# mm_robot_pcb_v2.net
KiCad netlist of a schematic drawn in EAGLE
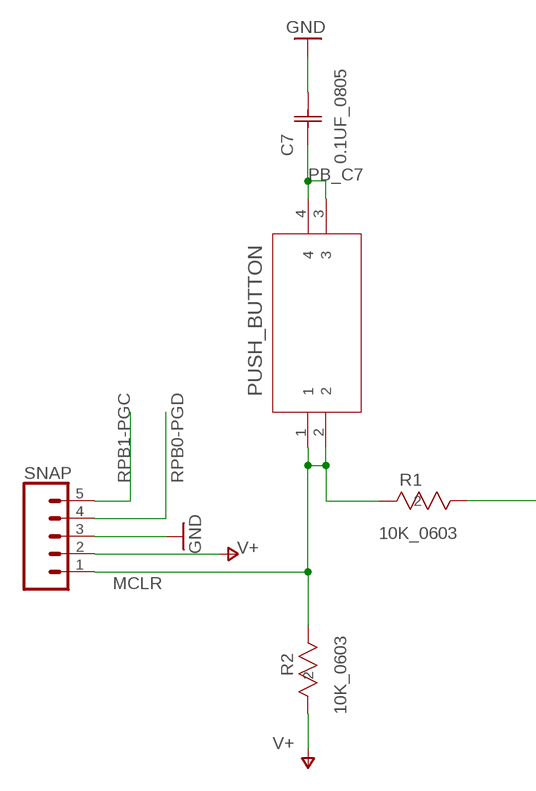
[diagram p0: schematic, sheet 1, part 1 of 2]
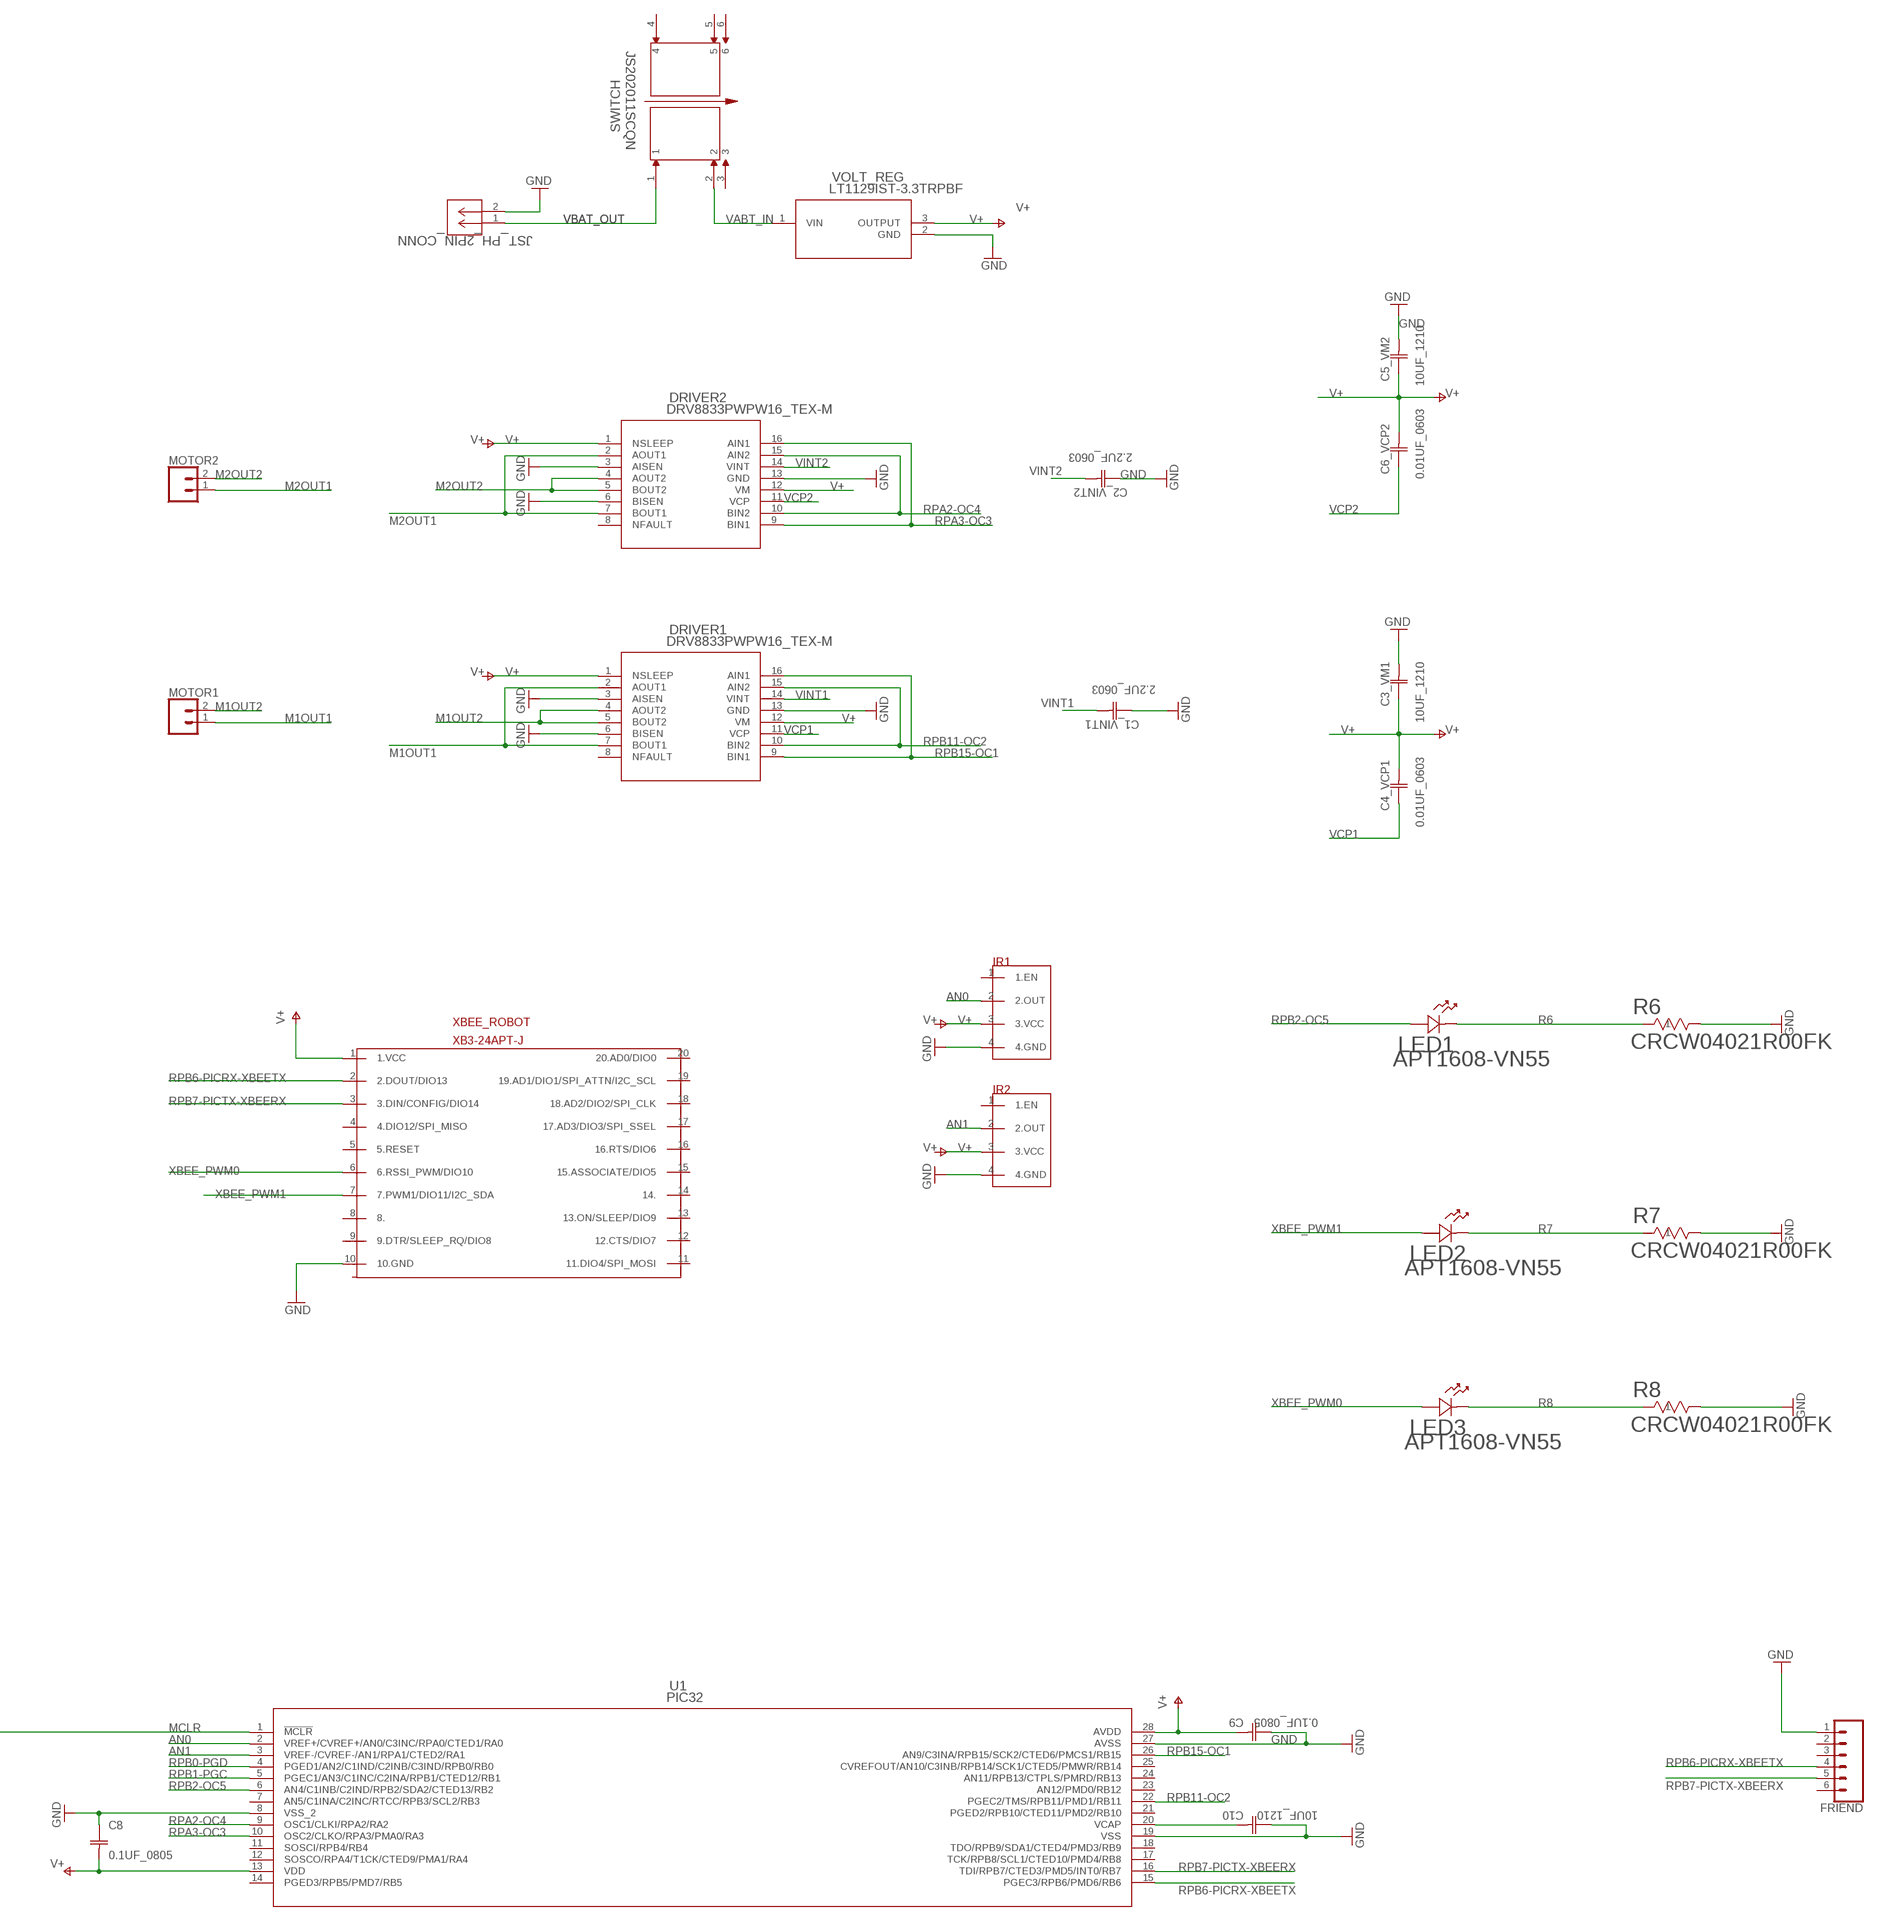
[diagram p1: schematic, sheet 1, part 2 of 2]

(export (version "E")
  (design (tool "Eeschema 10.0.6"))
  (components
    (comp (ref "C1_VINT1")
      (value "2.2UF_0603")
      (footprint "eagle-import:CAP_CL10_SAM")
      (fields
        (field (name "MANUFACTURER_PART_NUMBER") "CL10A225KP8NNNC")
        (field (name "COPYRIGHT") "Copyright (C) 2021 Ultra Librarian. All rights reserved.")
      )
      (libsource (lib "eagle-import") (part "CL10A225KP8NNNC"))
    )
    (comp (ref "C2_VINT2")
      (value "2.2UF_0603")
      (footprint "eagle-import:CAP_CL10_SAM")
      (fields
        (field (name "MANUFACTURER_PART_NUMBER") "CL10A225KP8NNNC")
        (field (name "COPYRIGHT") "Copyright (C) 2021 Ultra Librarian. All rights reserved.")
      )
      (libsource (lib "eagle-import") (part "CL10A225KP8NNNC"))
    )
    (comp (ref "C3_VM1")
      (value "10UF_1210")
      (footprint "eagle-import:CAP_TPS_B_AVX")
      (fields
        (field (name "MANUFACTURER_PART_NUMBER") "TPSB106K016R0500")
        (field (name "COPYRIGHT") "Copyright (C) 2021 Ultra Librarian. All rights reserved.")
      )
      (libsource (lib "eagle-import") (part "TPSB106K016R0500"))
    )
    (comp (ref "C4_VCP1")
      (value "0.01UF_0603")
      (footprint "eagle-import:CAP_01UF_0603_X7R_G_AVX")
      (libsource (lib "eagle-import") (part "01UF_CAP"))
    )
    (comp (ref "C5_VM2")
      (value "10UF_1210")
      (footprint "eagle-import:CAP_TPS_B_AVX")
      (fields
        (field (name "MANUFACTURER_PART_NUMBER") "TPSB106K016R0500")
        (field (name "COPYRIGHT") "Copyright (C) 2021 Ultra Librarian. All rights reserved.")
      )
      (libsource (lib "eagle-import") (part "TPSB106K016R0500"))
    )
    (comp (ref "C6_VCP2")
      (value "0.01UF_0603")
      (footprint "eagle-import:CAP_01UF_0603_X7R_G_AVX")
      (libsource (lib "eagle-import") (part "01UF_CAP"))
    )
    (comp (ref "C7")
      (value "0.1UF_0805")
      (footprint "eagle-import:CAP_C2012X7R2A104K125AA_TDK")
      (fields
        (field (name "MANUFACTURER_PART_NUMBER") "C2012X7R2A104K125AA")
        (field (name "COPYRIGHT") "Copyright (C) 2021 Ultra Librarian. All rights reserved.")
      )
      (libsource (lib "eagle-import") (part "C2012X7R2A104K125AA"))
    )
    (comp (ref "C8")
      (value "0.1UF_0805")
      (footprint "eagle-import:CAP_C2012X7R2A104K125AA_TDK")
      (fields
        (field (name "MANUFACTURER_PART_NUMBER") "C2012X7R2A104K125AA")
        (field (name "COPYRIGHT") "Copyright (C) 2021 Ultra Librarian. All rights reserved.")
      )
      (libsource (lib "eagle-import") (part "C2012X7R2A104K125AA"))
    )
    (comp (ref "C9")
      (value "0.1UF_0805")
      (footprint "eagle-import:CAP_C2012X7R2A104K125AA_TDK")
      (fields
        (field (name "MANUFACTURER_PART_NUMBER") "C2012X7R2A104K125AA")
        (field (name "COPYRIGHT") "Copyright (C) 2021 Ultra Librarian. All rights reserved.")
      )
      (libsource (lib "eagle-import") (part "C2012X7R2A104K125AA"))
    )
    (comp (ref "C10")
      (value "10UF_1210")
      (footprint "eagle-import:CAP_TPS_B_AVX")
      (fields
        (field (name "MANUFACTURER_PART_NUMBER") "TPSB106K016R0500")
        (field (name "COPYRIGHT") "Copyright (C) 2021 Ultra Librarian. All rights reserved.")
      )
      (libsource (lib "eagle-import") (part "TPSB106K016R0500"))
    )
    (comp (ref "DRIVER1")
      (value "DRV8833PWPW16_TEX-M")
      (footprint "eagle-import:PW16_TEX-M")
      (fields
        (field (name "MANUFACTURER_PART_NUMBER") "DRV8833PW")
        (field (name "COPYRIGHT") "Copyright (C) 2021 Ultra Librarian. All rights reserved.")
      )
      (libsource (lib "eagle-import") (part "DRV8833PWPW16_TEX-M"))
    )
    (comp (ref "DRIVER2")
      (value "DRV8833PWPW16_TEX-M")
      (footprint "eagle-import:PW16_TEX-M")
      (fields
        (field (name "MANUFACTURER_PART_NUMBER") "DRV8833PW")
        (field (name "COPYRIGHT") "Copyright (C) 2021 Ultra Librarian. All rights reserved.")
      )
      (libsource (lib "eagle-import") (part "DRV8833PWPW16_TEX-M"))
    )
    (comp (ref "FRIEND")
      (value "CONN_06LOCK")
      (footprint "eagle-import:1X06_LOCK")
      (libsource (lib "eagle-import") (part "CONN_06LOCK"))
    )
    (comp (ref "IR1")
      (value "GP2Y0A60SZLF")
      (footprint "eagle-import:1X04")
      (libsource (lib "eagle-import") (part "GP2Y0A60SZLF"))
    )
    (comp (ref "IR2")
      (value "GP2Y0A60SZLF")
      (footprint "eagle-import:1X04")
      (libsource (lib "eagle-import") (part "GP2Y0A60SZLF"))
    )
    (comp (ref "JST_PH_2PIN_CONN")
      (value "1769")
      (footprint "eagle-import:CONN_1769_ADA")
      (fields (field (name "COPYRIGHT") "Copyright (C) 2021 Ultra Librarian. All rights reserved."))
      (libsource (lib "eagle-import") (part "1769"))
    )
    (comp (ref "LED1")
      (value "APT1608-VN55")
      (footprint "eagle-import:LED_APT1608_KNB")
      (fields (field (name "COPYRIGHT") "Copyright (C) 2021 Ultra Librarian. All rights reserved."))
      (libsource (lib "eagle-import") (part "APT1608-VN55"))
    )
    (comp (ref "LED2")
      (value "APT1608-VN55")
      (footprint "eagle-import:LED_APT1608_KNB")
      (fields (field (name "COPYRIGHT") "Copyright (C) 2021 Ultra Librarian. All rights reserved."))
      (libsource (lib "eagle-import") (part "APT1608-VN55"))
    )
    (comp (ref "LED3")
      (value "APT1608-VN55")
      (footprint "eagle-import:LED_APT1608_KNB")
      (fields (field (name "COPYRIGHT") "Copyright (C) 2021 Ultra Librarian. All rights reserved."))
      (libsource (lib "eagle-import") (part "APT1608-VN55"))
    )
    (comp (ref "MOTOR1")
      (value "CONN_02")
      (footprint "eagle-import:1X02")
      (libsource (lib "eagle-import") (part "CONN_02"))
    )
    (comp (ref "MOTOR2")
      (value "CONN_02")
      (footprint "eagle-import:1X02")
      (libsource (lib "eagle-import") (part "CONN_02"))
    )
    (comp (ref "R1")
      (value "10K_0603")
      (footprint "eagle-import:RES0603_CRG_TYCO_TYC")
      (fields
        (field (name "MANUFACTURER_PART_NUMBER") "CRG0603F10K")
        (field (name "COPYRIGHT") "Copyright (C) 2021 Ultra Librarian. All rights reserved.")
      )
      (libsource (lib "eagle-import") (part "CRG0603F10K"))
    )
    (comp (ref "R2")
      (value "10K_0603")
      (footprint "eagle-import:RES0603_CRG_TYCO_TYC")
      (fields
        (field (name "MANUFACTURER_PART_NUMBER") "CRG0603F10K")
        (field (name "COPYRIGHT") "Copyright (C) 2021 Ultra Librarian. All rights reserved.")
      )
      (libsource (lib "eagle-import") (part "CRG0603F10K"))
    )
    (comp (ref "R6")
      (value "CRCW04021R00FK")
      (footprint "eagle-import:RES_CRCW0402_VIS")
      (fields (field (name "COPYRIGHT") "Copyright (C) 2021 Ultra Librarian. All rights reserved."))
      (libsource (lib "eagle-import") (part "CRCW04021R00FK"))
    )
    (comp (ref "R7")
      (value "CRCW04021R00FK")
      (footprint "eagle-import:RES_CRCW0402_VIS")
      (fields (field (name "COPYRIGHT") "Copyright (C) 2021 Ultra Librarian. All rights reserved."))
      (libsource (lib "eagle-import") (part "CRCW04021R00FK"))
    )
    (comp (ref "R8")
      (value "CRCW04021R00FK")
      (footprint "eagle-import:RES_CRCW0402_VIS")
      (fields (field (name "COPYRIGHT") "Copyright (C) 2021 Ultra Librarian. All rights reserved."))
      (libsource (lib "eagle-import") (part "CRCW04021R00FK"))
    )
    (comp (ref "SNAP")
      (value "CONN_05")
      (footprint "eagle-import:1X05")
      (libsource (lib "eagle-import") (part "CONN_05"))
    )
    (comp (ref "SWITCH")
      (value "JS202011SCQN")
      (footprint "eagle-import:SW_JS202011SCQN")
      (fields (field (name "COPYRIGHT") "Copyright (C) 2021 Ultra Librarian. All rights reserved."))
      (libsource (lib "eagle-import") (part "JS202011SCQN"))
    )
    (comp (ref "U1")
      (value "PIC32")
      (footprint "eagle-import:SSOP28_MC_MCH")
      (fields
        (field (name "MANUFACTURER_PART_NUMBER") "PIC32MX170F256B-I/SS")
        (field (name "COPYRIGHT") "Copyright (C) 2021 Ultra Librarian. All rights reserved.")
      )
      (libsource (lib "eagle-import") (part "PIC32MX170F256B-I/SS"))
    )
    (comp (ref "U2")
      (value "PUSH_BUTTON")
      (footprint "eagle-import:SMT_FS")
      (fields
        (field (name "MANUFACTURER_PART_NUMBER") "PTS526 SK15 SMTR2 LFS")
        (field (name "COPYRIGHT") "Copyright (C) 2021 Ultra Librarian. All rights reserved.")
      )
      (libsource (lib "eagle-import") (part "PTS526_SK15_SMTR2_LFS"))
    )
    (comp (ref "VOLT_REG")
      (value "LT1129IST-3.3TRPBF")
      (footprint "eagle-import:SOT-223_ST_LIT")
      (fields
        (field (name "MANUFACTURER_PART_NUMBER") "LT1129IST-3.3#TRPBF")
        (field (name "COPYRIGHT") "Copyright (C) 2021 Ultra Librarian. All rights reserved.")
      )
      (libsource (lib "eagle-import") (part "LT1129IST-3.3TRPBF"))
    )
    (comp (ref "XBEE_ROBOT")
      (value "XB3-24APT-J")
      (footprint "eagle-import:XB3-24APT-J")
      (libsource (lib "eagle-import") (part "XB3-24APT-J"))
    )
  )
  (nets
    (net (code "1") (name "/AN0") (class "Default")
      (node (ref "IR1") (pin "2") (pinfunction "2.OUT_2") (pintype "bidirectional"))
      (node (ref "U1") (pin "2") (pinfunction "VREF+/CVREF+/AN0/C3INC/RPA0/CTED1/RA0_2") (pintype "bidirectional"))
    )
    (net (code "2") (name "/AN1") (class "Default")
      (node (ref "IR2") (pin "2") (pinfunction "2.OUT_2") (pintype "bidirectional"))
      (node (ref "U1") (pin "3") (pinfunction "VREF-/CVREF-/AN1/RPA1/CTED2/RA1_3") (pintype "bidirectional"))
    )
    (net (code "3") (name "/M1OUT1") (class "Default")
      (node (ref "DRIVER1") (pin "2") (pinfunction "AOUT1_2") (pintype "output"))
      (node (ref "DRIVER1") (pin "7") (pinfunction "BOUT1_7") (pintype "output"))
      (node (ref "MOTOR1") (pin "1") (pinfunction "1_1") (pintype "passive"))
    )
    (net (code "4") (name "/M1OUT2") (class "Default")
      (node (ref "DRIVER1") (pin "4") (pinfunction "AOUT2_4") (pintype "output"))
      (node (ref "DRIVER1") (pin "5") (pinfunction "BOUT2_5") (pintype "output"))
      (node (ref "MOTOR1") (pin "2") (pinfunction "2_2") (pintype "passive"))
    )
    (net (code "5") (name "/M2OUT1") (class "Default")
      (node (ref "DRIVER2") (pin "2") (pinfunction "AOUT1_2") (pintype "output"))
      (node (ref "DRIVER2") (pin "7") (pinfunction "BOUT1_7") (pintype "output"))
      (node (ref "MOTOR2") (pin "1") (pinfunction "1_1") (pintype "passive"))
    )
    (net (code "6") (name "/M2OUT2") (class "Default")
      (node (ref "DRIVER2") (pin "4") (pinfunction "AOUT2_4") (pintype "output"))
      (node (ref "DRIVER2") (pin "5") (pinfunction "BOUT2_5") (pintype "output"))
      (node (ref "MOTOR2") (pin "2") (pinfunction "2_2") (pintype "passive"))
    )
    (net (code "7") (name "/MCLR") (class "Default")
      (node (ref "R1") (pin "1") (pinfunction "1_1") (pintype "passive"))
      (node (ref "R1") (pin "2") (pinfunction "2_2") (pintype "passive"))
      (node (ref "R2") (pin "1") (pinfunction "1_1") (pintype "passive"))
      (node (ref "SNAP") (pin "1") (pinfunction "1_1") (pintype "passive"))
      (node (ref "U1") (pin "1") (pinfunction "~{MCLR}_1") (pintype "bidirectional"))
      (node (ref "U2") (pin "1") (pinfunction "1_1") (pintype "passive"))
      (node (ref "U2") (pin "2") (pinfunction "2_2") (pintype "passive"))
    )
    (net (code "8") (name "/PB_C7") (class "Default")
      (node (ref "C7") (pin "1") (pinfunction "1_1") (pintype "passive"))
      (node (ref "U2") (pin "3") (pinfunction "3_3") (pintype "passive"))
      (node (ref "U2") (pin "4") (pinfunction "4_4") (pintype "passive"))
    )
    (net (code "9") (name "/R6") (class "Default")
      (node (ref "LED1") (pin "1") (pinfunction "1_1") (pintype "passive"))
      (node (ref "R6") (pin "1") (pinfunction "1_1") (pintype "passive"))
    )
    (net (code "10") (name "/R7") (class "Default")
      (node (ref "LED2") (pin "1") (pinfunction "1_1") (pintype "passive"))
      (node (ref "R7") (pin "1") (pinfunction "1_1") (pintype "passive"))
    )
    (net (code "11") (name "/R8") (class "Default")
      (node (ref "LED3") (pin "1") (pinfunction "1_1") (pintype "passive"))
      (node (ref "R8") (pin "1") (pinfunction "1_1") (pintype "passive"))
    )
    (net (code "12") (name "/RPA2-OC4") (class "Default")
      (node (ref "DRIVER2") (pin "10") (pinfunction "BIN2_10") (pintype "input"))
      (node (ref "DRIVER2") (pin "15") (pinfunction "AIN2_15") (pintype "input"))
      (node (ref "U1") (pin "9") (pinfunction "OSC1/CLKI/RPA2/RA2_9") (pintype "bidirectional"))
    )
    (net (code "13") (name "/RPA3-OC3") (class "Default")
      (node (ref "DRIVER2") (pin "16") (pinfunction "AIN1_16") (pintype "input"))
      (node (ref "DRIVER2") (pin "9") (pinfunction "BIN1_9") (pintype "input"))
      (node (ref "U1") (pin "10") (pinfunction "OSC2/CLKO/RPA3/PMA0/RA3_10") (pintype "bidirectional"))
    )
    (net (code "14") (name "/RPB0-PGD") (class "Default")
      (node (ref "SNAP") (pin "4") (pinfunction "4_4") (pintype "passive"))
      (node (ref "U1") (pin "4") (pinfunction "PGED1/AN2/C1IND/C2INB/C3IND/RPB0/RB0_4") (pintype "bidirectional"))
    )
    (net (code "15") (name "/RPB1-PGC") (class "Default")
      (node (ref "SNAP") (pin "5") (pinfunction "5_5") (pintype "passive"))
      (node (ref "U1") (pin "5") (pinfunction "PGEC1/AN3/C1INC/C2INA/RPB1/CTED12/RB1_5") (pintype "bidirectional"))
    )
    (net (code "16") (name "/RPB2-OC5") (class "Default")
      (node (ref "LED1") (pin "2") (pinfunction "2_2") (pintype "passive"))
      (node (ref "U1") (pin "6") (pinfunction "AN4/C1INB/C2IND/RPB2/SDA2/CTED13/RB2_6") (pintype "bidirectional"))
    )
    (net (code "17") (name "/RPB6-PICRX-XBEETX") (class "Default")
      (node (ref "FRIEND") (pin "4") (pinfunction "4_4") (pintype "passive"))
      (node (ref "U1") (pin "15") (pinfunction "PGEC3/RPB6/PMD6/RB6_15") (pintype "bidirectional"))
      (node (ref "XBEE_ROBOT") (pin "2") (pinfunction "2.DOUT/DIO13_2") (pintype "bidirectional"))
    )
    (net (code "18") (name "/RPB7-PICTX-XBEERX") (class "Default")
      (node (ref "FRIEND") (pin "5") (pinfunction "5_5") (pintype "passive"))
      (node (ref "U1") (pin "16") (pinfunction "TDI/RPB7/CTED3/PMD5/INT0/RB7_16") (pintype "bidirectional"))
      (node (ref "XBEE_ROBOT") (pin "3") (pinfunction "3.DIN/CONFIG/DIO14_3") (pintype "bidirectional"))
    )
    (net (code "19") (name "/RPB11-OC2") (class "Default")
      (node (ref "DRIVER1") (pin "10") (pinfunction "BIN2_10") (pintype "input"))
      (node (ref "DRIVER1") (pin "15") (pinfunction "AIN2_15") (pintype "input"))
      (node (ref "U1") (pin "22") (pinfunction "PGEC2/TMS/RPB11/PMD1/RB11_22") (pintype "bidirectional"))
    )
    (net (code "20") (name "/RPB15-OC1") (class "Default")
      (node (ref "DRIVER1") (pin "16") (pinfunction "AIN1_16") (pintype "input"))
      (node (ref "DRIVER1") (pin "9") (pinfunction "BIN1_9") (pintype "input"))
      (node (ref "U1") (pin "26") (pinfunction "AN9/C3INA/RPB15/SCK2/CTED6/PMCS1/RB15_26") (pintype "bidirectional"))
    )
    (net (code "21") (name "/VABT_IN") (class "Default")
      (node (ref "SWITCH") (pin "2") (pinfunction "2_2") (pintype "passive"))
      (node (ref "VOLT_REG") (pin "1") (pinfunction "VIN_1") (pintype "input"))
    )
    (net (code "22") (name "/VBAT_OUT") (class "Default")
      (node (ref "JST_PH_2PIN_CONN") (pin "1") (pinfunction "1_1") (pintype "passive"))
      (node (ref "SWITCH") (pin "1") (pinfunction "1_1") (pintype "passive"))
    )
    (net (code "23") (name "/VCP1") (class "Default")
      (node (ref "C4_VCP1") (pin "1") (pinfunction "1_1") (pintype "passive"))
      (node (ref "DRIVER1") (pin "11") (pinfunction "VCP_11") (pintype "bidirectional"))
    )
    (net (code "24") (name "/VCP2") (class "Default")
      (node (ref "C6_VCP2") (pin "1") (pinfunction "1_1") (pintype "passive"))
      (node (ref "DRIVER2") (pin "11") (pinfunction "VCP_11") (pintype "bidirectional"))
    )
    (net (code "25") (name "/VINT1") (class "Default")
      (node (ref "C1_VINT1") (pin "2") (pinfunction "2_2") (pintype "passive"))
      (node (ref "DRIVER1") (pin "14") (pinfunction "VINT_14") (pintype "passive"))
    )
    (net (code "26") (name "/VINT2") (class "Default")
      (node (ref "C2_VINT2") (pin "2") (pinfunction "2_2") (pintype "passive"))
      (node (ref "DRIVER2") (pin "14") (pinfunction "VINT_14") (pintype "passive"))
    )
    (net (code "27") (name "/XBEE_PWM0") (class "Default")
      (node (ref "LED3") (pin "2") (pinfunction "2_2") (pintype "passive"))
      (node (ref "XBEE_ROBOT") (pin "6") (pinfunction "6.RSSI_PWM/DIO10_6") (pintype "bidirectional"))
    )
    (net (code "28") (name "/XBEE_PWM1") (class "Default")
      (node (ref "LED2") (pin "2") (pinfunction "2_2") (pintype "passive"))
      (node (ref "XBEE_ROBOT") (pin "7") (pinfunction "7.PWM1/DIO11/I2C_SDA_7") (pintype "bidirectional"))
    )
    (net (code "29") (name "GND") (class "Default")
      (node (ref "C10") (pin "1") (pinfunction "11_1") (pintype "passive"))
      (node (ref "C1_VINT1") (pin "1") (pinfunction "1_1") (pintype "passive"))
      (node (ref "C2_VINT2") (pin "1") (pinfunction "1_1") (pintype "passive"))
      (node (ref "C3_VM1") (pin "2") (pinfunction "12_2") (pintype "passive"))
      (node (ref "C5_VM2") (pin "2") (pinfunction "12_2") (pintype "passive"))
      (node (ref "C7") (pin "2") (pinfunction "2_2") (pintype "passive"))
      (node (ref "C8") (pin "1") (pinfunction "1_1") (pintype "passive"))
      (node (ref "C9") (pin "1") (pinfunction "1_1") (pintype "passive"))
      (node (ref "DRIVER1") (pin "13") (pinfunction "GND_13") (pintype "power_in"))
      (node (ref "DRIVER1") (pin "3") (pinfunction "AISEN_3") (pintype "bidirectional"))
      (node (ref "DRIVER1") (pin "6") (pinfunction "BISEN_6") (pintype "bidirectional"))
      (node (ref "DRIVER2") (pin "13") (pinfunction "GND_13") (pintype "power_in"))
      (node (ref "DRIVER2") (pin "3") (pinfunction "AISEN_3") (pintype "bidirectional"))
      (node (ref "DRIVER2") (pin "6") (pinfunction "BISEN_6") (pintype "bidirectional"))
      (node (ref "FRIEND") (pin "1") (pinfunction "1_1") (pintype "passive"))
      (node (ref "IR1") (pin "4") (pinfunction "4.GND_4") (pintype "bidirectional"))
      (node (ref "IR2") (pin "4") (pinfunction "4.GND_4") (pintype "bidirectional"))
      (node (ref "JST_PH_2PIN_CONN") (pin "2") (pinfunction "2_2") (pintype "passive"))
      (node (ref "R6") (pin "2") (pinfunction "2_2") (pintype "passive"))
      (node (ref "R7") (pin "2") (pinfunction "2_2") (pintype "passive"))
      (node (ref "R8") (pin "2") (pinfunction "2_2") (pintype "passive"))
      (node (ref "SNAP") (pin "3") (pinfunction "3_3") (pintype "passive"))
      (node (ref "U1") (pin "19") (pinfunction "VSS_19") (pintype "power_in"))
      (node (ref "U1") (pin "27") (pinfunction "AVSS_27") (pintype "power_in"))
      (node (ref "U1") (pin "8") (pinfunction "VSS_2_8") (pintype "power_in"))
      (node (ref "VOLT_REG") (pin "2") (pinfunction "GND_2") (pintype "power_in"))
      (node (ref "XBEE_ROBOT") (pin "10") (pinfunction "10.GND_10") (pintype "bidirectional"))
    )
    (net (code "30") (name "Net-(C10-12)") (class "Default")
      (node (ref "C10") (pin "2") (pinfunction "12_2") (pintype "passive"))
      (node (ref "U1") (pin "20") (pinfunction "VCAP_20") (pintype "power_in"))
    )
    (net (code "31") (name "V+") (class "Default")
      (node (ref "C3_VM1") (pin "1") (pinfunction "11_1") (pintype "passive"))
      (node (ref "C4_VCP1") (pin "2") (pinfunction "2_2") (pintype "passive"))
      (node (ref "C5_VM2") (pin "1") (pinfunction "11_1") (pintype "passive"))
      (node (ref "C6_VCP2") (pin "2") (pinfunction "2_2") (pintype "passive"))
      (node (ref "C8") (pin "2") (pinfunction "2_2") (pintype "passive"))
      (node (ref "C9") (pin "2") (pinfunction "2_2") (pintype "passive"))
      (node (ref "DRIVER1") (pin "1") (pinfunction "NSLEEP_1") (pintype "input"))
      (node (ref "DRIVER1") (pin "12") (pinfunction "VM_12") (pintype "power_in"))
      (node (ref "DRIVER2") (pin "1") (pinfunction "NSLEEP_1") (pintype "input"))
      (node (ref "DRIVER2") (pin "12") (pinfunction "VM_12") (pintype "power_in"))
      (node (ref "IR1") (pin "3") (pinfunction "3.VCC_3") (pintype "bidirectional"))
      (node (ref "IR2") (pin "3") (pinfunction "3.VCC_3") (pintype "bidirectional"))
      (node (ref "R2") (pin "2") (pinfunction "2_2") (pintype "passive"))
      (node (ref "SNAP") (pin "2") (pinfunction "2_2") (pintype "passive"))
      (node (ref "U1") (pin "13") (pinfunction "VDD_13") (pintype "power_in"))
      (node (ref "U1") (pin "28") (pinfunction "AVDD_28") (pintype "power_in"))
      (node (ref "VOLT_REG") (pin "3") (pinfunction "OUTPUT_3") (pintype "output"))
      (node (ref "XBEE_ROBOT") (pin "1") (pinfunction "1.VCC_1") (pintype "bidirectional"))
    )
    (net (code "32") (name "unconnected-(DRIVER1-NFAULT-Pad8)") (class "Default")
      (node (ref "DRIVER1") (pin "8") (pinfunction "NFAULT_8") (pintype "output"))
    )
    (net (code "33") (name "unconnected-(DRIVER2-NFAULT-Pad8)") (class "Default")
      (node (ref "DRIVER2") (pin "8") (pinfunction "NFAULT_8") (pintype "output"))
    )
    (net (code "34") (name "unconnected-(FRIEND-Pad2)") (class "Default")
      (node (ref "FRIEND") (pin "2") (pinfunction "2_2") (pintype "passive"))
    )
    (net (code "35") (name "unconnected-(FRIEND-Pad3)") (class "Default")
      (node (ref "FRIEND") (pin "3") (pinfunction "3_3") (pintype "passive"))
    )
    (net (code "36") (name "unconnected-(FRIEND-Pad6)") (class "Default")
      (node (ref "FRIEND") (pin "6") (pinfunction "6_6") (pintype "passive"))
    )
    (net (code "37") (name "unconnected-(IR1-1.EN-Pad1)") (class "Default")
      (node (ref "IR1") (pin "1") (pinfunction "1.EN_1") (pintype "bidirectional"))
    )
    (net (code "38") (name "unconnected-(IR2-1.EN-Pad1)") (class "Default")
      (node (ref "IR2") (pin "1") (pinfunction "1.EN_1") (pintype "bidirectional"))
    )
    (net (code "39") (name "unconnected-(SWITCH-Pad3)") (class "Default")
      (node (ref "SWITCH") (pin "3") (pinfunction "3_3") (pintype "passive"))
    )
    (net (code "40") (name "unconnected-(SWITCH-Pad4)") (class "Default")
      (node (ref "SWITCH") (pin "4") (pinfunction "4_4") (pintype "passive"))
    )
    (net (code "41") (name "unconnected-(SWITCH-Pad5)") (class "Default")
      (node (ref "SWITCH") (pin "5") (pinfunction "5_5") (pintype "passive"))
    )
    (net (code "42") (name "unconnected-(SWITCH-Pad6)") (class "Default")
      (node (ref "SWITCH") (pin "6") (pinfunction "6_6") (pintype "passive"))
    )
    (net (code "43") (name "unconnected-(U1-AN5{slash}C1INA{slash}C2INC{slash}RTCC{slash}RPB3{slash}SCL2{slash}RB3-Pad7)") (class "Default")
      (node (ref "U1") (pin "7") (pinfunction "AN5/C1INA/C2INC/RTCC/RPB3/SCL2/RB3_7") (pintype "bidirectional"))
    )
    (net (code "44") (name "unconnected-(U1-AN11{slash}RPB13{slash}CTPLS{slash}PMRD{slash}RB13-Pad24)") (class "Default")
      (node (ref "U1") (pin "24") (pinfunction "AN11/RPB13/CTPLS/PMRD/RB13_24") (pintype "bidirectional"))
    )
    (net (code "45") (name "unconnected-(U1-AN12{slash}PMD0{slash}RB12-Pad23)") (class "Default")
      (node (ref "U1") (pin "23") (pinfunction "AN12/PMD0/RB12_23") (pintype "bidirectional"))
    )
    (net (code "46") (name "unconnected-(U1-CVREFOUT{slash}AN10{slash}C3INB{slash}RPB14{slash}SCK1{slash}CTED5{slash}PMWR{slash}RB14-Pad25)") (class "Default")
      (node (ref "U1") (pin "25") (pinfunction "CVREFOUT/AN10/C3INB/RPB14/SCK1/CTED5/PMWR/RB14_25") (pintype "bidirectional"))
    )
    (net (code "47") (name "unconnected-(U1-PGED2{slash}RPB10{slash}CTED11{slash}PMD2{slash}RB10-Pad21)") (class "Default")
      (node (ref "U1") (pin "21") (pinfunction "PGED2/RPB10/CTED11/PMD2/RB10_21") (pintype "bidirectional"))
    )
    (net (code "48") (name "unconnected-(U1-PGED3{slash}RPB5{slash}PMD7{slash}RB5-Pad14)") (class "Default")
      (node (ref "U1") (pin "14") (pinfunction "PGED3/RPB5/PMD7/RB5_14") (pintype "bidirectional"))
    )
    (net (code "49") (name "unconnected-(U1-SOSCI{slash}RPB4{slash}RB4-Pad11)") (class "Default")
      (node (ref "U1") (pin "11") (pinfunction "SOSCI/RPB4/RB4_11") (pintype "bidirectional"))
    )
    (net (code "50") (name "unconnected-(U1-SOSCO{slash}RPA4{slash}T1CK{slash}CTED9{slash}PMA1{slash}RA4-Pad12)") (class "Default")
      (node (ref "U1") (pin "12") (pinfunction "SOSCO/RPA4/T1CK/CTED9/PMA1/RA4_12") (pintype "bidirectional"))
    )
    (net (code "51") (name "unconnected-(U1-TCK{slash}RPB8{slash}SCL1{slash}CTED10{slash}PMD4{slash}RB8-Pad17)") (class "Default")
      (node (ref "U1") (pin "17") (pinfunction "TCK/RPB8/SCL1/CTED10/PMD4/RB8_17") (pintype "bidirectional"))
    )
    (net (code "52") (name "unconnected-(U1-TDO{slash}RPB9{slash}SDA1{slash}CTED4{slash}PMD3{slash}RB9-Pad18)") (class "Default")
      (node (ref "U1") (pin "18") (pinfunction "TDO/RPB9/SDA1/CTED4/PMD3/RB9_18") (pintype "bidirectional"))
    )
    (net (code "53") (name "unconnected-(XBEE_ROBOT-4.DIO12{slash}SPI_MISO-Pad4)") (class "Default")
      (node (ref "XBEE_ROBOT") (pin "4") (pinfunction "4.DIO12/SPI_MISO_4") (pintype "bidirectional"))
    )
    (net (code "54") (name "unconnected-(XBEE_ROBOT-5.RESET-Pad5)") (class "Default")
      (node (ref "XBEE_ROBOT") (pin "5") (pinfunction "5.RESET_5") (pintype "bidirectional"))
    )
    (net (code "55") (name "unconnected-(XBEE_ROBOT-8.-Pad8)") (class "Default")
      (node (ref "XBEE_ROBOT") (pin "8") (pinfunction "8._8") (pintype "bidirectional"))
    )
    (net (code "56") (name "unconnected-(XBEE_ROBOT-9.DTR{slash}SLEEP_RQ{slash}DIO8-Pad9)") (class "Default")
      (node (ref "XBEE_ROBOT") (pin "9") (pinfunction "9.DTR/SLEEP_RQ/DIO8_9") (pintype "bidirectional"))
    )
    (net (code "57") (name "unconnected-(XBEE_ROBOT-11.DIO4{slash}SPI_MOSI-Pad11)") (class "Default")
      (node (ref "XBEE_ROBOT") (pin "11") (pinfunction "11.DIO4/SPI_MOSI_11") (pintype "bidirectional"))
    )
    (net (code "58") (name "unconnected-(XBEE_ROBOT-12.CTS{slash}DIO7-Pad12)") (class "Default")
      (node (ref "XBEE_ROBOT") (pin "12") (pinfunction "12.CTS/DIO7_12") (pintype "bidirectional"))
    )
    (net (code "59") (name "unconnected-(XBEE_ROBOT-13.ON{slash}SLEEP{slash}DIO9-Pad13)") (class "Default")
      (node (ref "XBEE_ROBOT") (pin "13") (pinfunction "13.ON/SLEEP/DIO9_13") (pintype "bidirectional"))
    )
    (net (code "60") (name "unconnected-(XBEE_ROBOT-14.-Pad14)") (class "Default")
      (node (ref "XBEE_ROBOT") (pin "14") (pinfunction "14._14") (pintype "bidirectional"))
    )
    (net (code "61") (name "unconnected-(XBEE_ROBOT-15.ASSOCIATE{slash}DIO5-Pad15)") (class "Default")
      (node (ref "XBEE_ROBOT") (pin "15") (pinfunction "15.ASSOCIATE/DIO5_15") (pintype "bidirectional"))
    )
    (net (code "62") (name "unconnected-(XBEE_ROBOT-16.RTS{slash}DIO6-Pad16)") (class "Default")
      (node (ref "XBEE_ROBOT") (pin "16") (pinfunction "16.RTS/DIO6_16") (pintype "bidirectional"))
    )
    (net (code "63") (name "unconnected-(XBEE_ROBOT-17.AD3{slash}DIO3{slash}SPI_SSEL-Pad17)") (class "Default")
      (node (ref "XBEE_ROBOT") (pin "17") (pinfunction "17.AD3/DIO3/SPI_SSEL_17") (pintype "bidirectional"))
    )
    (net (code "64") (name "unconnected-(XBEE_ROBOT-18.AD2{slash}DIO2{slash}SPI_CLK-Pad18)") (class "Default")
      (node (ref "XBEE_ROBOT") (pin "18") (pinfunction "18.AD2/DIO2/SPI_CLK_18") (pintype "bidirectional"))
    )
    (net (code "65") (name "unconnected-(XBEE_ROBOT-19.AD1{slash}DIO1{slash}SPI_ATTN{slash}I2C_SCL-Pad19)") (class "Default")
      (node (ref "XBEE_ROBOT") (pin "19") (pinfunction "19.AD1/DIO1/SPI_ATTN/I2C_SCL_19") (pintype "bidirectional"))
    )
    (net (code "66") (name "unconnected-(XBEE_ROBOT-20.AD0{slash}DIO0-Pad20)") (class "Default")
      (node (ref "XBEE_ROBOT") (pin "20") (pinfunction "20.AD0/DIO0_20") (pintype "bidirectional"))
    )
  )
)
